# 06-BatteryManagement.net
KiCad netlist of a schematic drawn in Altium Designer
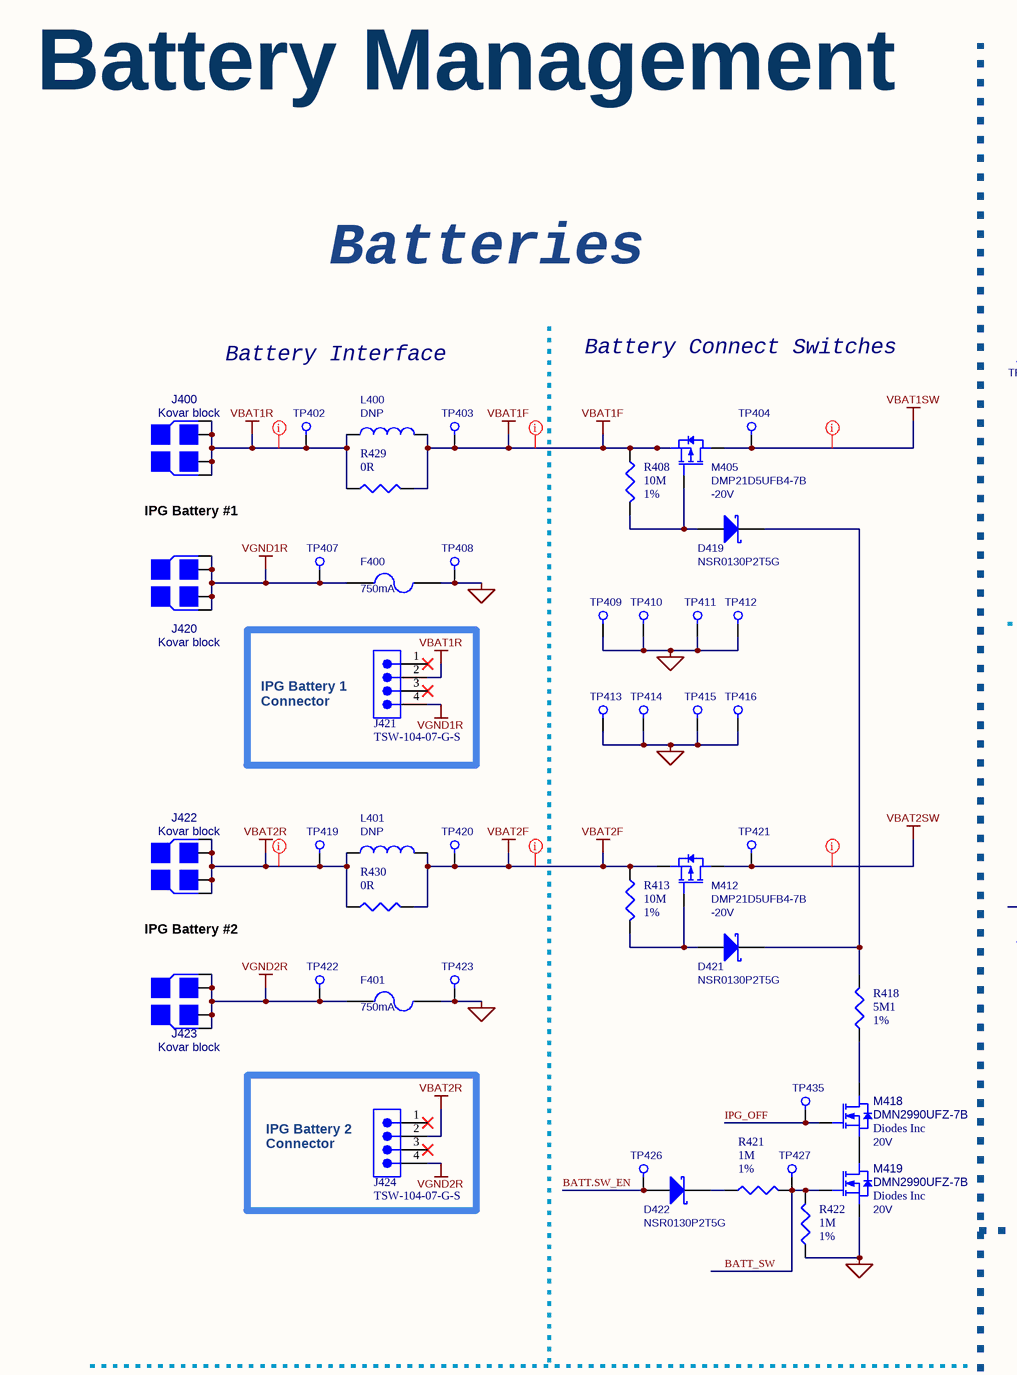
[diagram p0: 06-BatteryManagement.SchDoc, left]
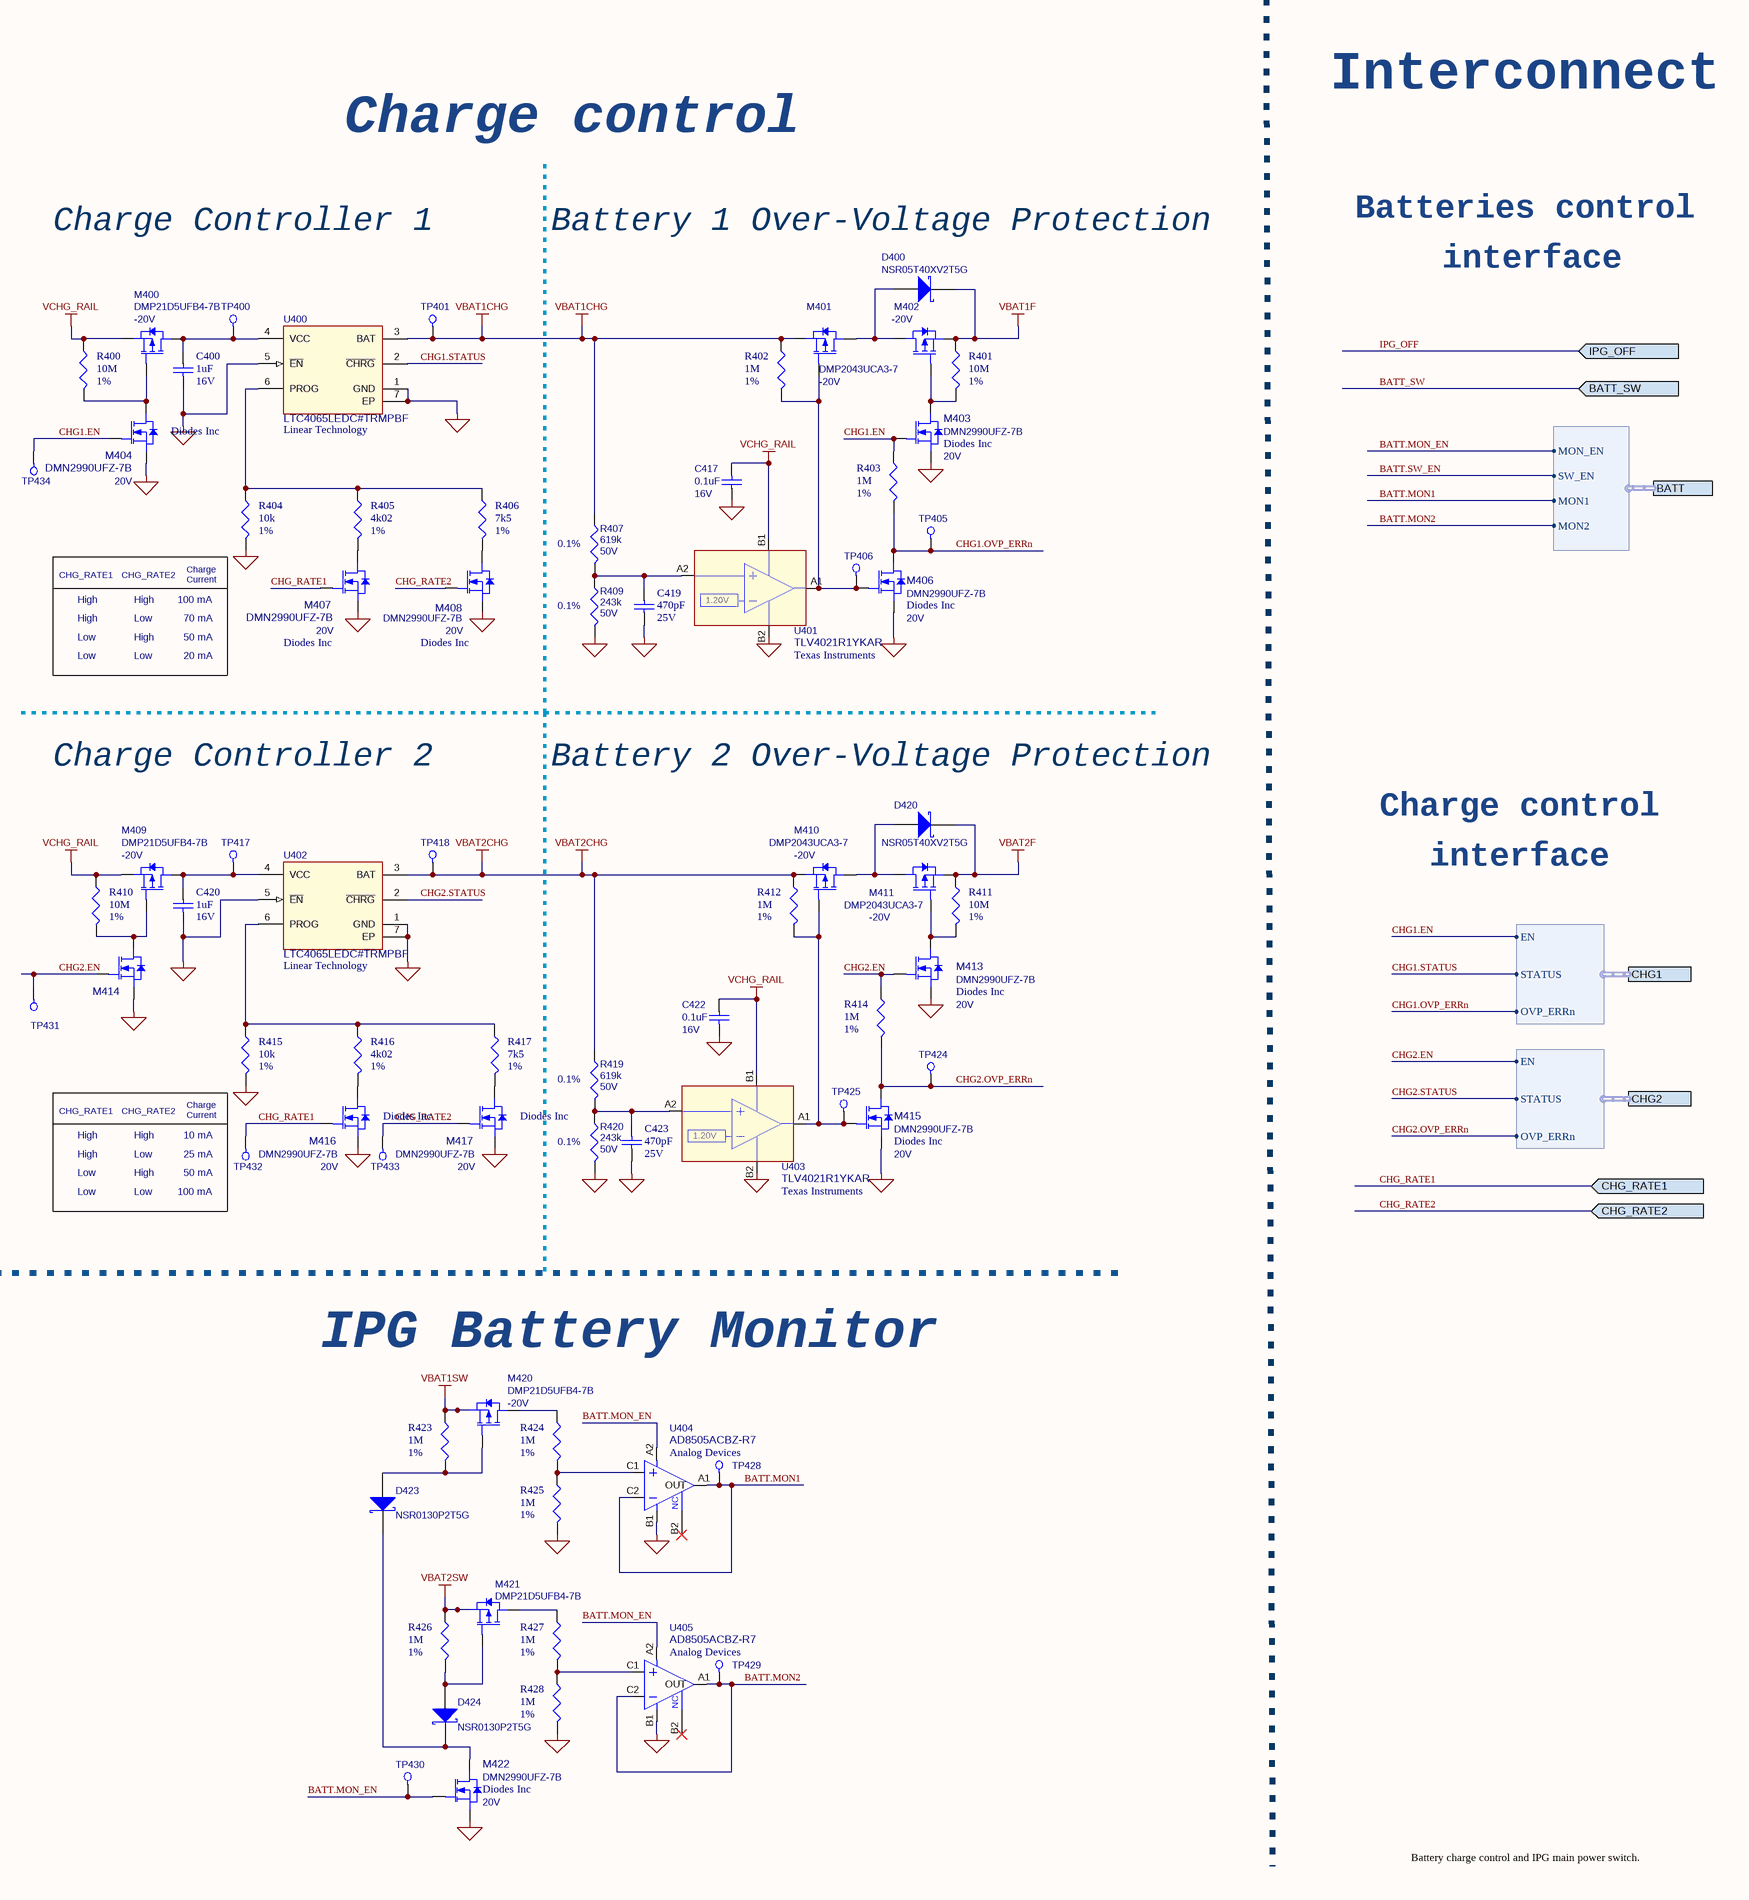
[diagram p1: 06-BatteryManagement.SchDoc, right]

(export (version "E")
  (design (tool "Eeschema 10.0.6"))
  (components
    (comp (ref "C400")
      (value "1uF")
      (footprint "C0201_C")
      (fields
        (field (name "MANUFACTURER") "Murata")
        (field (name "MANUFACTURER PART NUMBER") "GRM033R61C105ME15D")
        (field (name "RATED DC VOLTAGE (URDC)") "16V")
      )
      (libsource (lib "MP-LIBRARY") (part "GRM033R61C105ME15D"))
    )
    (comp (ref "C417")
      (value "0.1uF")
      (footprint "CAP0402_REDUCED")
      (description "Capacitor, 0.1uF, X7R, 16V, 10%, 0402, Implant-grade")
      (fields
        (field (name "MANUFACTURER") "Murata")
        (field (name "RATING") "16V")
        (field (name "MANUFACTURER PART NUMBER") "GCM155R71C104KA55")
      )
      (libsource (lib "MP-LIBRARY") (part "GCM155R71C104KA55"))
    )
    (comp (ref "C419")
      (value "470pF")
      (footprint "C0201_C")
      (fields
        (field (name "MANUFACTURER") "Murata")
        (field (name "MANUFACTURER PART NUMBER") "GCM033R71E471KA03D")
        (field (name "RATED DC VOLTAGE (URDC)") "25V")
      )
      (libsource (lib "MP-LIBRARY") (part "GCM033R71E471KA03D"))
    )
    (comp (ref "C420")
      (value "1uF")
      (footprint "C0201_C")
      (fields
        (field (name "MANUFACTURER") "Murata")
        (field (name "MANUFACTURER PART NUMBER") "GRM033R61C105ME15D")
        (field (name "RATED DC VOLTAGE (URDC)") "16V")
      )
      (libsource (lib "MP-LIBRARY") (part "GRM033R61C105ME15D"))
    )
    (comp (ref "C422")
      (value "0.1uF")
      (footprint "CAP0402_REDUCED")
      (description "Capacitor, 0.1uF, X7R, 16V, 10%, 0402, Implant-grade")
      (fields
        (field (name "MANUFACTURER") "Murata")
        (field (name "RATING") "16V")
        (field (name "MANUFACTURER PART NUMBER") "GCM155R71C104KA55")
      )
      (libsource (lib "MP-LIBRARY") (part "GCM155R71C104KA55"))
    )
    (comp (ref "C423")
      (value "470pF")
      (footprint "C0201_C")
      (fields
        (field (name "MANUFACTURER") "Murata")
        (field (name "MANUFACTURER PART NUMBER") "GCM033R71E471KA03D")
        (field (name "RATED DC VOLTAGE (URDC)") "25V")
      )
      (libsource (lib "MP-LIBRARY") (part "GCM033R71E471KA03D"))
    )
    (comp (ref "D400")
      (value "NSR05T40XV2T5G")
      (footprint "STM_SOD-523_R")
      (description "Schottky, 40V, 500mA, 530mV, SOD-523")
      (fields (field (name "MANUFACTURER") "ON Semiconductor"))
      (libsource (lib "MP-LIBRARY") (part "NSR05T40XV2T5G"))
    )
    (comp (ref "D419")
      (value "NSR0130P2T5G")
      (footprint "ONSC_SOD-923_CASE514AB")
      (description "Schottky, 30V, 100mA, 385mV, 200mW, SOD-923")
      (fields (field (name "MANUFACTURER") "ON Semiconductor"))
      (libsource (lib "MP-LIBRARY") (part "NSR0130P2T5G"))
    )
    (comp (ref "D420")
      (value "NSR05T40XV2T5G")
      (footprint "STM_SOD-523_R")
      (description "Schottky, 40V, 500mA, 530mV, SOD-523")
      (fields (field (name "MANUFACTURER") "ON Semiconductor"))
      (libsource (lib "MP-LIBRARY") (part "NSR05T40XV2T5G"))
    )
    (comp (ref "D421")
      (value "NSR0130P2T5G")
      (footprint "ONSC_SOD-923_CASE514AB")
      (description "Schottky, 30V, 100mA, 385mV, 200mW, SOD-923")
      (fields (field (name "MANUFACTURER") "ON Semiconductor"))
      (libsource (lib "MP-LIBRARY") (part "NSR0130P2T5G"))
    )
    (comp (ref "D422")
      (value "NSR0130P2T5G")
      (footprint "ONSC_SOD-923_CASE514AB")
      (description "Schottky, 30V, 100mA, 385mV, 200mW, SOD-923")
      (fields (field (name "MANUFACTURER") "ON Semiconductor"))
      (libsource (lib "MP-LIBRARY") (part "NSR0130P2T5G"))
    )
    (comp (ref "D423")
      (value "NSR0130P2T5G")
      (footprint "ONSC_SOD-923_CASE514AB")
      (description "Schottky, 30V, 100mA, 385mV, 200mW, SOD-923")
      (fields (field (name "MANUFACTURER") "ON Semiconductor"))
      (libsource (lib "MP-LIBRARY") (part "NSR0130P2T5G"))
    )
    (comp (ref "D424")
      (value "NSR0130P2T5G")
      (footprint "ONSC_SOD-923_CASE514AB")
      (description "Schottky, 30V, 100mA, 385mV, 200mW, SOD-923")
      (fields (field (name "MANUFACTURER") "ON Semiconductor"))
      (libsource (lib "MP-LIBRARY") (part "NSR0130P2T5G"))
    )
    (comp (ref "F400")
      (value "750mA")
      (footprint "LITTELFUSE_440series_1206_REDUCED")
      (description "Fuse, 750mA, 63V, 1206")
      (fields
        (field (name "MANUFACTURER") "Littelfuse")
        (field (name "MANUFACTURER PART NUMBER") "0440.750WR")
      )
      (libsource (lib "MP-LIBRARY") (part "0440.750WR"))
    )
    (comp (ref "F401")
      (value "750mA")
      (footprint "LITTELFUSE_440series_1206_REDUCED")
      (description "Fuse, 750mA, 63V, 1206")
      (fields
        (field (name "MANUFACTURER") "Littelfuse")
        (field (name "MANUFACTURER PART NUMBER") "0440.750WR")
      )
      (libsource (lib "MP-LIBRARY") (part "0440.750WR"))
    )
    (comp (ref "J400")
      (value "Kovar block")
      (footprint "KOVAR_BLOCK_PAD_1.53MM")
      (description "Kovar block, TBD")
      (fields (field (name "MANUFACTURER") "TBD") (field (name "Comment") "Kovar Block"))
      (libsource (lib "MP-LIBRARY") (part "Kovar Block"))
    )
    (comp (ref "J420")
      (value "Kovar block")
      (footprint "KOVAR_BLOCK_PAD_1.53MM")
      (description "Kovar block, TBD")
      (fields (field (name "MANUFACTURER") "TBD") (field (name "Comment") "Kovar Block"))
      (libsource (lib "MP-LIBRARY") (part "Kovar Block"))
    )
    (comp (ref "J421")
      (value "TSW-104-07-G-S")
      (footprint "SMTC-TSW-104-07-X-S")
      (fields (field (name "MANUFACTURER") "Samtec") (field (name "PARTNUMBER") "TSW-106-07-G-S"))
      (libsource (lib "MP-LIBRARY") (part "TSW-104-07-G-S"))
    )
    (comp (ref "J422")
      (value "Kovar block")
      (footprint "KOVAR_BLOCK_PAD_1.53MM")
      (description "Kovar block, TBD")
      (fields (field (name "MANUFACTURER") "TBD") (field (name "Comment") "Kovar Block"))
      (libsource (lib "MP-LIBRARY") (part "Kovar Block"))
    )
    (comp (ref "J423")
      (value "Kovar block")
      (footprint "KOVAR_BLOCK_PAD_1.53MM")
      (description "Kovar block, TBD")
      (fields (field (name "MANUFACTURER") "TBD") (field (name "Comment") "Kovar Block"))
      (libsource (lib "MP-LIBRARY") (part "Kovar Block"))
    )
    (comp (ref "J424")
      (value "TSW-104-07-G-S")
      (footprint "SMTC-TSW-104-07-X-S")
      (fields (field (name "MANUFACTURER") "Samtec") (field (name "PARTNUMBER") "TSW-106-07-G-S"))
      (libsource (lib "MP-LIBRARY") (part "TSW-104-07-G-S"))
    )
    (comp (ref "L400")
      (value "DNP")
      (footprint "L0402_C")
      (description "DNP: Inductor, DNP, 0402")
      (libsource (lib "MP-LIBRARY") (part "IND_DNP_0402"))
    )
    (comp (ref "L401")
      (value "DNP")
      (footprint "L0402_C")
      (description "DNP: Inductor, DNP, 0402")
      (libsource (lib "MP-LIBRARY") (part "IND_DNP_0402"))
    )
    (comp (ref "M400")
      (value "DMP21D5UFB4-7B")
      (footprint "DIODESINC_X2-DFN1006-3_REDUCED")
      (description "MOSFET, P-chan, -20V, -400mA, X2-DFN1006-3")
      (fields (field (name "MANUFACTURER") "Diodes Inc") (field (name "RATING") "-20V"))
      (libsource (lib "MP-LIBRARY") (part "DMP21D5UFB4-7B"))
    )
    (comp (ref "M401")
      (value "DMP2043UCA3-7")
      (footprint "DIODESINC_X2-DSN1010-3_CUSTOMPIN")
      (description "MOSFET, P-chan, -20V, -3.4A, DFN1010-3")
      (fields (field (name "MANUFACTURER") "Diodes Inc") (field (name "RATING") "-20V"))
      (libsource (lib "MP-LIBRARY") (part "DMP2043UCA3-7"))
    )
    (comp (ref "M402")
      (value "DMP2043UCA3-7")
      (footprint "DIODESINC_X2-DSN1010-3_CUSTOMPIN")
      (description "MOSFET, P-chan, -20V, -3.4A, DFN1010-3")
      (fields (field (name "MANUFACTURER") "Diodes Inc") (field (name "RATING") "-20V"))
      (libsource (lib "MP-LIBRARY") (part "DMP2043UCA3-7"))
    )
    (comp (ref "M403")
      (value "DMN2990UFZ-7B")
      (footprint "DIODESINC_X2-DFN0606-3")
      (description "MOSFET, N-Chan, 20V, 170mA, DFN0606")
      (fields (field (name "MANUFACTURER") "Diodes Inc") (field (name "RATING") "20V"))
      (libsource (lib "MP-LIBRARY") (part "DMN2990UFZ-7B"))
    )
    (comp (ref "M404")
      (value "DMN2990UFZ-7B")
      (footprint "DIODESINC_X2-DFN0606-3")
      (description "MOSFET, N-Chan, 20V, 170mA, DFN0606")
      (fields (field (name "RATING") "20V") (field (name "MANUFACTURER") "Diodes Inc"))
      (libsource (lib "MP-LIBRARY") (part "DMN2990UFZ-7B"))
    )
    (comp (ref "M405")
      (value "DMP21D5UFB4-7B")
      (footprint "DIODESINC_X2-DFN1006-3_REDUCED")
      (description "MOSFET, P-chan, -20V, -400mA, X2-DFN1006-3")
      (fields (field (name "MANUFACTURER") "Diodes Inc") (field (name "RATING") "-20V"))
      (libsource (lib "MP-LIBRARY") (part "DMP21D5UFB4-7B"))
    )
    (comp (ref "M406")
      (value "DMN2990UFZ-7B")
      (footprint "DIODESINC_X2-DFN0606-3")
      (description "MOSFET, N-Chan, 20V, 170mA, DFN0606")
      (fields (field (name "MANUFACTURER") "Diodes Inc") (field (name "RATING") "20V"))
      (libsource (lib "MP-LIBRARY") (part "DMN2990UFZ-7B"))
    )
    (comp (ref "M407")
      (value "DMN2990UFZ-7B")
      (footprint "DIODESINC_X2-DFN0606-3")
      (description "MOSFET, N-Chan, 20V, 170mA, DFN0606")
      (fields (field (name "RATING") "20V") (field (name "MANUFACTURER") "Diodes Inc"))
      (libsource (lib "MP-LIBRARY") (part "DMN2990UFZ-7B"))
    )
    (comp (ref "M408")
      (value "DMN2990UFZ-7B")
      (footprint "DIODESINC_X2-DFN0606-3")
      (description "MOSFET, N-Chan, 20V, 170mA, DFN0606")
      (fields (field (name "RATING") "20V") (field (name "MANUFACTURER") "Diodes Inc"))
      (libsource (lib "MP-LIBRARY") (part "DMN2990UFZ-7B"))
    )
    (comp (ref "M409")
      (value "DMP21D5UFB4-7B")
      (footprint "DIODESINC_X2-DFN1006-3_REDUCED")
      (description "MOSFET, P-chan, -20V, -400mA, X2-DFN1006-3")
      (fields (field (name "MANUFACTURER") "Diodes Inc") (field (name "RATING") "-20V"))
      (libsource (lib "MP-LIBRARY") (part "DMP21D5UFB4-7B"))
    )
    (comp (ref "M410")
      (value "DMP2043UCA3-7")
      (footprint "DIODESINC_X2-DSN1010-3_CUSTOMPIN")
      (description "MOSFET, P-chan, -20V, -3.4A, DFN1010-3")
      (fields (field (name "MANUFACTURER") "Diodes Inc") (field (name "RATING") "-20V"))
      (libsource (lib "MP-LIBRARY") (part "DMP2043UCA3-7"))
    )
    (comp (ref "M411")
      (value "DMP2043UCA3-7")
      (footprint "DIODESINC_X2-DSN1010-3_CUSTOMPIN")
      (description "MOSFET, P-chan, -20V, -3.4A, DFN1010-3")
      (fields (field (name "MANUFACTURER") "Diodes Inc") (field (name "RATING") "-20V"))
      (libsource (lib "MP-LIBRARY") (part "DMP2043UCA3-7"))
    )
    (comp (ref "M412")
      (value "DMP21D5UFB4-7B")
      (footprint "DIODESINC_X2-DFN1006-3_REDUCED")
      (description "MOSFET, P-chan, -20V, -400mA, X2-DFN1006-3")
      (fields (field (name "MANUFACTURER") "Diodes Inc") (field (name "RATING") "-20V"))
      (libsource (lib "MP-LIBRARY") (part "DMP21D5UFB4-7B"))
    )
    (comp (ref "M413")
      (value "DMN2990UFZ-7B")
      (footprint "DIODESINC_X2-DFN0606-3")
      (description "MOSFET, N-Chan, 20V, 170mA, DFN0606")
      (fields (field (name "MANUFACTURER") "Diodes Inc") (field (name "RATING") "20V"))
      (libsource (lib "MP-LIBRARY") (part "DMN2990UFZ-7B"))
    )
    (comp (ref "M414")
      (value "DMN2990UFZ-7B")
      (footprint "DIODESINC_X2-DFN0606-3")
      (description "MOSFET, N-Chan, 20V, 170mA, DFN0606")
      (fields (field (name "MANUFACTURER") "Diodes Inc"))
      (libsource (lib "MP-LIBRARY") (part "DMN2990UFZ-7B"))
    )
    (comp (ref "M415")
      (value "DMN2990UFZ-7B")
      (footprint "DIODESINC_X2-DFN0606-3")
      (description "MOSFET, N-Chan, 20V, 170mA, DFN0606")
      (fields (field (name "MANUFACTURER") "Diodes Inc") (field (name "RATING") "20V"))
      (libsource (lib "MP-LIBRARY") (part "DMN2990UFZ-7B"))
    )
    (comp (ref "M416")
      (value "DMN2990UFZ-7B")
      (footprint "DIODESINC_X2-DFN0606-3")
      (description "MOSFET, N-Chan, 20V, 170mA, DFN0606")
      (fields (field (name "RATING") "20V") (field (name "MANUFACTURER") "Diodes Inc"))
      (libsource (lib "MP-LIBRARY") (part "DMN2990UFZ-7B"))
    )
    (comp (ref "M417")
      (value "DMN2990UFZ-7B")
      (footprint "DIODESINC_X2-DFN0606-3")
      (description "MOSFET, N-Chan, 20V, 170mA, DFN0606")
      (fields (field (name "RATING") "20V") (field (name "MANUFACTURER") "Diodes Inc"))
      (libsource (lib "MP-LIBRARY") (part "DMN2990UFZ-7B"))
    )
    (comp (ref "M418")
      (value "DMN2990UFZ-7B")
      (footprint "DIODESINC_X2-DFN0606-3")
      (description "MOSFET, N-Chan, 20V, 170mA, DFN0606")
      (fields (field (name "MANUFACTURER") "Diodes Inc") (field (name "RATING") "20V"))
      (libsource (lib "MP-LIBRARY") (part "DMN2990UFZ-7B"))
    )
    (comp (ref "M419")
      (value "DMN2990UFZ-7B")
      (footprint "DIODESINC_X2-DFN0606-3")
      (description "MOSFET, N-Chan, 20V, 170mA, DFN0606")
      (fields (field (name "MANUFACTURER") "Diodes Inc") (field (name "RATING") "20V"))
      (libsource (lib "MP-LIBRARY") (part "DMN2990UFZ-7B"))
    )
    (comp (ref "M420")
      (value "DMP21D5UFB4-7B")
      (footprint "DIODESINC_X2-DFN1006-3_REDUCED")
      (description "MOSFET, P-chan, -20V, -400mA, X2-DFN1006-3")
      (fields (field (name "MANUFACTURER") "Diodes Inc") (field (name "RATING") "-20V"))
      (libsource (lib "MP-LIBRARY") (part "DMP21D5UFB4-7B"))
    )
    (comp (ref "M421")
      (value "DMP21D5UFB4-7B")
      (footprint "DIODESINC_X2-DFN1006-3_REDUCED")
      (description "MOSFET, P-chan, -20V, -400mA, X2-DFN1006-3")
      (fields (field (name "MANUFACTURER") "Diodes Inc"))
      (libsource (lib "MP-LIBRARY") (part "DMP21D5UFB4-7B"))
    )
    (comp (ref "M422")
      (value "DMN2990UFZ-7B")
      (footprint "DIODESINC_X2-DFN0606-3")
      (description "MOSFET, N-Chan, 20V, 170mA, DFN0606")
      (fields (field (name "MANUFACTURER") "Diodes Inc") (field (name "RATING") "20V"))
      (libsource (lib "MP-LIBRARY") (part "DMN2990UFZ-7B"))
    )
    (comp (ref "R400")
      (value "10M")
      (footprint "R0201_C")
      (fields
        (field (name "MANUFACTURER") "Vishay Draloric")
        (field (name "MANUFACTURER PART NUMBER") "CRCW020110M0FNED")
        (field (name "TOLERANCE") "1%")
        (field (name "POWER") "50mW")
      )
      (libsource (lib "MP-LIBRARY") (part "CRCW020110M0FNED"))
    )
    (comp (ref "R401")
      (value "10M")
      (footprint "R0201_C")
      (fields
        (field (name "MANUFACTURER") "Vishay Draloric")
        (field (name "MANUFACTURER PART NUMBER") "CRCW020110M0FNED")
        (field (name "TOLERANCE") "1%")
        (field (name "POWER") "50mW")
      )
      (libsource (lib "MP-LIBRARY") (part "CRCW020110M0FNED"))
    )
    (comp (ref "R402")
      (value "1M")
      (footprint "R0201_C")
      (fields
        (field (name "MANUFACTURER") "Vishay")
        (field (name "MANUFACTURER PART NUMBER") "CRCW02011M00FNED")
        (field (name "TOLERANCE") "1%")
        (field (name "POWER") "50mW")
      )
      (libsource (lib "MP-LIBRARY") (part "CRCW02011M00FNED"))
    )
    (comp (ref "R403")
      (value "1M")
      (footprint "R0201_C")
      (fields
        (field (name "MANUFACTURER") "Vishay")
        (field (name "MANUFACTURER PART NUMBER") "CRCW02011M00FNED")
        (field (name "TOLERANCE") "1%")
        (field (name "POWER") "50mW")
      )
      (libsource (lib "MP-LIBRARY") (part "CRCW02011M00FNED"))
    )
    (comp (ref "R404")
      (value "10k")
      (footprint "R0201_C")
      (fields
        (field (name "MANUFACTURER") "Vishay")
        (field (name "MANUFACTURER PART NUMBER") "CRCW020110K0FNED")
        (field (name "TOLERANCE") "1%")
        (field (name "POWER") "50mW")
      )
      (libsource (lib "MP-LIBRARY") (part "CRCW020110K0FNED"))
    )
    (comp (ref "R405")
      (value "4k02")
      (footprint "R0201_C")
      (fields
        (field (name "MANUFACTURER") "Vishay")
        (field (name "MANUFACTURER PART NUMBER") "CRCW02014K02FNED")
        (field (name "TOLERANCE") "1%")
        (field (name "POWER") "50mW")
      )
      (libsource (lib "MP-LIBRARY") (part "CRCW02014K02FNED"))
    )
    (comp (ref "R406")
      (value "7k5")
      (footprint "R0201_C")
      (fields
        (field (name "MANUFACTURER") "Vishay")
        (field (name "MANUFACTURER PART NUMBER") "CRCW02017K50FNED")
        (field (name "TOLERANCE") "1%")
        (field (name "POWER") "50mW")
      )
      (libsource (lib "MP-LIBRARY") (part "CRCW02017K50FNED"))
    )
    (comp (ref "R407")
      (value "619k")
      (footprint "RES0402_REDUCED")
      (description "Resistor, 619k, 0.1%, 0402")
      (fields
        (field (name "MANUFACTURER") "Vishay")
        (field (name "RATING") "50V")
        (field (name "PRECISION") "0.1%")
        (field (name "MANUFACTURER PART NUMBER") "MCS0402MD6193BE000")
      )
      (libsource (lib "MP-LIBRARY") (part "MCS0402MD6193BE000"))
    )
    (comp (ref "R408")
      (value "10M")
      (footprint "R0201_C")
      (fields
        (field (name "MANUFACTURER") "Vishay Draloric")
        (field (name "MANUFACTURER PART NUMBER") "CRCW020110M0FNED")
        (field (name "TOLERANCE") "1%")
        (field (name "POWER") "50mW")
      )
      (libsource (lib "MP-LIBRARY") (part "CRCW020110M0FNED"))
    )
    (comp (ref "R409")
      (value "243k")
      (footprint "RES0402_REDUCED")
      (description "Resistor, 243k, 0.1%, 0402")
      (fields
        (field (name "MANUFACTURER") "TE Connectivity")
        (field (name "RATING") "50V")
        (field (name "PRECISION") "0.1%")
        (field (name "MANUFACTURER PART NUMBER") "RP73PF1E243KBTDF")
      )
      (libsource (lib "MP-LIBRARY") (part "RP73PF1E243KBTD"))
    )
    (comp (ref "R410")
      (value "10M")
      (footprint "R0201_C")
      (fields
        (field (name "MANUFACTURER") "Vishay Draloric")
        (field (name "MANUFACTURER PART NUMBER") "CRCW020110M0FNED")
        (field (name "TOLERANCE") "1%")
        (field (name "POWER") "50mW")
      )
      (libsource (lib "MP-LIBRARY") (part "CRCW020110M0FNED"))
    )
    (comp (ref "R411")
      (value "10M")
      (footprint "R0201_C")
      (fields
        (field (name "MANUFACTURER") "Vishay Draloric")
        (field (name "MANUFACTURER PART NUMBER") "CRCW020110M0FNED")
        (field (name "TOLERANCE") "1%")
        (field (name "POWER") "50mW")
      )
      (libsource (lib "MP-LIBRARY") (part "CRCW020110M0FNED"))
    )
    (comp (ref "R412")
      (value "1M")
      (footprint "R0201_C")
      (fields
        (field (name "MANUFACTURER") "Vishay")
        (field (name "MANUFACTURER PART NUMBER") "CRCW02011M00FNED")
        (field (name "TOLERANCE") "1%")
        (field (name "POWER") "50mW")
      )
      (libsource (lib "MP-LIBRARY") (part "CRCW02011M00FNED"))
    )
    (comp (ref "R413")
      (value "10M")
      (footprint "R0201_C")
      (fields
        (field (name "MANUFACTURER") "Vishay Draloric")
        (field (name "MANUFACTURER PART NUMBER") "CRCW020110M0FNED")
        (field (name "TOLERANCE") "1%")
        (field (name "POWER") "50mW")
      )
      (libsource (lib "MP-LIBRARY") (part "CRCW020110M0FNED"))
    )
    (comp (ref "R414")
      (value "1M")
      (footprint "R0201_C")
      (fields
        (field (name "MANUFACTURER") "Vishay")
        (field (name "MANUFACTURER PART NUMBER") "CRCW02011M00FNED")
        (field (name "TOLERANCE") "1%")
        (field (name "POWER") "50mW")
      )
      (libsource (lib "MP-LIBRARY") (part "CRCW02011M00FNED"))
    )
    (comp (ref "R415")
      (value "10k")
      (footprint "R0201_C")
      (fields
        (field (name "MANUFACTURER") "Vishay")
        (field (name "MANUFACTURER PART NUMBER") "CRCW020110K0FNED")
        (field (name "TOLERANCE") "1%")
        (field (name "POWER") "50mW")
      )
      (libsource (lib "MP-LIBRARY") (part "CRCW020110K0FNED"))
    )
    (comp (ref "R416")
      (value "4k02")
      (footprint "R0201_C")
      (fields
        (field (name "MANUFACTURER") "Vishay")
        (field (name "MANUFACTURER PART NUMBER") "CRCW02014K02FNED")
        (field (name "TOLERANCE") "1%")
        (field (name "POWER") "50mW")
      )
      (libsource (lib "MP-LIBRARY") (part "CRCW02014K02FNED"))
    )
    (comp (ref "R417")
      (value "7k5")
      (footprint "R0201_C")
      (fields
        (field (name "MANUFACTURER") "Vishay")
        (field (name "MANUFACTURER PART NUMBER") "CRCW02017K50FNED")
        (field (name "TOLERANCE") "1%")
        (field (name "POWER") "50mW")
      )
      (libsource (lib "MP-LIBRARY") (part "CRCW02017K50FNED"))
    )
    (comp (ref "R418")
      (value "5M1")
      (footprint "R0201_C")
      (fields
        (field (name "MANUFACTURER") "Vishay Draloric")
        (field (name "MANUFACTURER PART NUMBER") "CRCW02015M10FNED")
        (field (name "TOLERANCE") "1%")
        (field (name "POWER") "50mW")
      )
      (libsource (lib "MP-LIBRARY") (part "CRCW02015M10FNED"))
    )
    (comp (ref "R419")
      (value "619k")
      (footprint "RES0402_REDUCED")
      (description "Resistor, 619k, 0.1%, 0402")
      (fields
        (field (name "MANUFACTURER") "Vishay")
        (field (name "RATING") "50V")
        (field (name "PRECISION") "0.1%")
        (field (name "MANUFACTURER PART NUMBER") "MCS0402MD6193BE000")
      )
      (libsource (lib "MP-LIBRARY") (part "MCS0402MD6193BE000"))
    )
    (comp (ref "R420")
      (value "243k")
      (footprint "RES0402_REDUCED")
      (description "Resistor, 243k, 0.1%, 0402")
      (fields
        (field (name "MANUFACTURER") "TE Connectivity")
        (field (name "RATING") "50V")
        (field (name "PRECISION") "0.1%")
        (field (name "MANUFACTURER PART NUMBER") "RP73PF1E243KBTDF")
      )
      (libsource (lib "MP-LIBRARY") (part "RP73PF1E243KBTD"))
    )
    (comp (ref "R421")
      (value "1M")
      (footprint "R0201_C")
      (fields
        (field (name "MANUFACTURER") "Vishay")
        (field (name "MANUFACTURER PART NUMBER") "CRCW02011M00FNED")
        (field (name "TOLERANCE") "1%")
        (field (name "POWER") "50mW")
      )
      (libsource (lib "MP-LIBRARY") (part "CRCW02011M00FNED"))
    )
    (comp (ref "R422")
      (value "1M")
      (footprint "R0201_C")
      (fields
        (field (name "MANUFACTURER") "Vishay")
        (field (name "MANUFACTURER PART NUMBER") "CRCW02011M00FNED")
        (field (name "TOLERANCE") "1%")
        (field (name "POWER") "50mW")
      )
      (libsource (lib "MP-LIBRARY") (part "CRCW02011M00FNED"))
    )
    (comp (ref "R423")
      (value "1M")
      (footprint "R0201_C")
      (fields
        (field (name "MANUFACTURER") "Vishay")
        (field (name "MANUFACTURER PART NUMBER") "CRCW02011M00FNED")
        (field (name "TOLERANCE") "1%")
        (field (name "POWER") "50mW")
      )
      (libsource (lib "MP-LIBRARY") (part "CRCW02011M00FNED"))
    )
    (comp (ref "R424")
      (value "1M")
      (footprint "R0201_C")
      (fields
        (field (name "MANUFACTURER") "Vishay")
        (field (name "MANUFACTURER PART NUMBER") "CRCW02011M00FNED")
        (field (name "TOLERANCE") "1%")
        (field (name "POWER") "50mW")
      )
      (libsource (lib "MP-LIBRARY") (part "CRCW02011M00FNED"))
    )
    (comp (ref "R425")
      (value "1M")
      (footprint "R0201_C")
      (fields
        (field (name "MANUFACTURER") "Vishay")
        (field (name "MANUFACTURER PART NUMBER") "CRCW02011M00FNED")
        (field (name "TOLERANCE") "1%")
        (field (name "POWER") "50mW")
      )
      (libsource (lib "MP-LIBRARY") (part "CRCW02011M00FNED"))
    )
    (comp (ref "R426")
      (value "1M")
      (footprint "R0201_C")
      (fields
        (field (name "MANUFACTURER") "Vishay")
        (field (name "MANUFACTURER PART NUMBER") "CRCW02011M00FNED")
        (field (name "TOLERANCE") "1%")
        (field (name "POWER") "50mW")
      )
      (libsource (lib "MP-LIBRARY") (part "CRCW02011M00FNED"))
    )
    (comp (ref "R427")
      (value "1M")
      (footprint "R0201_C")
      (fields
        (field (name "MANUFACTURER") "Vishay")
        (field (name "MANUFACTURER PART NUMBER") "CRCW02011M00FNED")
        (field (name "TOLERANCE") "1%")
        (field (name "POWER") "50mW")
      )
      (libsource (lib "MP-LIBRARY") (part "CRCW02011M00FNED"))
    )
    (comp (ref "R428")
      (value "1M")
      (footprint "R0201_C")
      (fields
        (field (name "MANUFACTURER") "Vishay")
        (field (name "MANUFACTURER PART NUMBER") "CRCW02011M00FNED")
        (field (name "TOLERANCE") "1%")
        (field (name "POWER") "50mW")
      )
      (libsource (lib "MP-LIBRARY") (part "CRCW02011M00FNED"))
    )
    (comp (ref "R429")
      (value "0R")
      (footprint "R0201_C")
      (description "Fixed Resistor, Metal Glaze/thick Film, 0.05W, 0ohm, Surface Mount, 0201")
      (fields
        (field (name "MANUFACTURER") "Vishay")
        (field (name "MANUFACTURER PART NUMBER") "CRCW02010000Z0ED")
      )
      (libsource (lib "MP-LIBRARY") (part "CRCW02010000Z0ED"))
    )
    (comp (ref "R430")
      (value "0R")
      (footprint "R0201_C")
      (description "Fixed Resistor, Metal Glaze/thick Film, 0.05W, 0ohm, Surface Mount, 0201")
      (fields
        (field (name "MANUFACTURER") "Vishay")
        (field (name "MANUFACTURER PART NUMBER") "CRCW02010000Z0ED")
      )
      (libsource (lib "MP-LIBRARY") (part "CRCW02010000Z0ED"))
    )
    (comp (ref "TP400")
      (value "Test Point")
      (footprint "testpad_0.9mm")
      (description "Test pad, 0.90mm circular pad")
      (libsource (lib "MP-LIBRARY") (part "Test Point"))
    )
    (comp (ref "TP401")
      (value "Test Point")
      (footprint "testpad_0.9mm")
      (description "Test pad, 0.90mm circular pad")
      (libsource (lib "MP-LIBRARY") (part "Test Point"))
    )
    (comp (ref "TP402")
      (value "Test Point")
      (footprint "testpad_0.9mm")
      (description "Test pad, 0.90mm circular pad")
      (libsource (lib "MP-LIBRARY") (part "Test Point"))
    )
    (comp (ref "TP403")
      (value "Test Point")
      (footprint "testpad_0.9mm")
      (description "Test pad, 0.90mm circular pad")
      (libsource (lib "MP-LIBRARY") (part "Test Point"))
    )
    (comp (ref "TP404")
      (value "Test Point")
      (footprint "testpad_0.9mm")
      (description "Test pad, 0.90mm circular pad")
      (libsource (lib "MP-LIBRARY") (part "Test Point"))
    )
    (comp (ref "TP405")
      (value "Test Point")
      (footprint "testpad_0.9mm")
      (description "Test pad, 0.90mm circular pad")
      (libsource (lib "MP-LIBRARY") (part "Test Point"))
    )
    (comp (ref "TP406")
      (value "Test Point")
      (footprint "testpad_0.9mm")
      (description "Test pad, 0.90mm circular pad")
      (libsource (lib "MP-LIBRARY") (part "Test Point"))
    )
    (comp (ref "TP407")
      (value "Test Point")
      (footprint "testpad_0.9mm")
      (description "Test pad, 0.90mm circular pad")
      (libsource (lib "MP-LIBRARY") (part "Test Point"))
    )
    (comp (ref "TP408")
      (value "Test Point")
      (footprint "testpad_0.9mm")
      (description "Test pad, 0.90mm circular pad")
      (libsource (lib "MP-LIBRARY") (part "Test Point"))
    )
    (comp (ref "TP409")
      (value "Test Point")
      (footprint "testpad_0.9mm")
      (description "Test pad, 0.90mm circular pad")
      (libsource (lib "MP-LIBRARY") (part "Test Point"))
    )
    (comp (ref "TP410")
      (value "Test Point")
      (footprint "testpad_0.9mm")
      (description "Test pad, 0.90mm circular pad")
      (libsource (lib "MP-LIBRARY") (part "Test Point"))
    )
    (comp (ref "TP411")
      (value "Test Point")
      (footprint "testpad_0.9mm")
      (description "Test pad, 0.90mm circular pad")
      (libsource (lib "MP-LIBRARY") (part "Test Point"))
    )
    (comp (ref "TP412")
      (value "Test Point")
      (footprint "testpad_0.9mm")
      (description "Test pad, 0.90mm circular pad")
      (libsource (lib "MP-LIBRARY") (part "Test Point"))
    )
    (comp (ref "TP413")
      (value "Test Point")
      (footprint "testpad_0.9mm")
      (description "Test pad, 0.90mm circular pad")
      (libsource (lib "MP-LIBRARY") (part "Test Point"))
    )
    (comp (ref "TP414")
      (value "Test Point")
      (footprint "testpad_0.9mm")
      (description "Test pad, 0.90mm circular pad")
      (libsource (lib "MP-LIBRARY") (part "Test Point"))
    )
    (comp (ref "TP415")
      (value "Test Point")
      (footprint "testpad_0.9mm")
      (description "Test pad, 0.90mm circular pad")
      (libsource (lib "MP-LIBRARY") (part "Test Point"))
    )
    (comp (ref "TP416")
      (value "Test Point")
      (footprint "testpad_0.9mm")
      (description "Test pad, 0.90mm circular pad")
      (libsource (lib "MP-LIBRARY") (part "Test Point"))
    )
    (comp (ref "TP417")
      (value "Test Point")
      (footprint "testpad_0.9mm")
      (description "Test pad, 0.90mm circular pad")
      (libsource (lib "MP-LIBRARY") (part "Test Point"))
    )
    (comp (ref "TP418")
      (value "Test Point")
      (footprint "testpad_0.9mm")
      (description "Test pad, 0.90mm circular pad")
      (libsource (lib "MP-LIBRARY") (part "Test Point"))
    )
    (comp (ref "TP419")
      (value "Test Point")
      (footprint "testpad_0.9mm")
      (description "Test pad, 0.90mm circular pad")
      (libsource (lib "MP-LIBRARY") (part "Test Point"))
    )
    (comp (ref "TP420")
      (value "Test Point")
      (footprint "testpad_0.9mm")
      (description "Test pad, 0.90mm circular pad")
      (libsource (lib "MP-LIBRARY") (part "Test Point"))
    )
    (comp (ref "TP421")
      (value "Test Point")
      (footprint "testpad_0.9mm")
      (description "Test pad, 0.90mm circular pad")
      (libsource (lib "MP-LIBRARY") (part "Test Point"))
    )
    (comp (ref "TP422")
      (value "Test Point")
      (footprint "testpad_0.9mm")
      (description "Test pad, 0.90mm circular pad")
      (libsource (lib "MP-LIBRARY") (part "Test Point"))
    )
    (comp (ref "TP423")
      (value "Test Point")
      (footprint "testpad_0.9mm")
      (description "Test pad, 0.90mm circular pad")
      (libsource (lib "MP-LIBRARY") (part "Test Point"))
    )
    (comp (ref "TP424")
      (value "Test Point")
      (footprint "testpad_0.9mm")
      (description "Test pad, 0.90mm circular pad")
      (libsource (lib "MP-LIBRARY") (part "Test Point"))
    )
    (comp (ref "TP425")
      (value "Test Point")
      (footprint "testpad_0.9mm")
      (description "Test pad, 0.90mm circular pad")
      (libsource (lib "MP-LIBRARY") (part "Test Point"))
    )
    (comp (ref "TP426")
      (value "Test Point")
      (footprint "testpad_0.9mm")
      (description "Test pad, 0.90mm circular pad")
      (libsource (lib "MP-LIBRARY") (part "Test Point"))
    )
    (comp (ref "TP427")
      (value "Test Point")
      (footprint "testpad_0.9mm")
      (description "Test pad, 0.90mm circular pad")
      (libsource (lib "MP-LIBRARY") (part "Test Point"))
    )
    (comp (ref "TP428")
      (value "Test Point")
      (footprint "testpad_0.9mm")
      (description "Test pad, 0.90mm circular pad")
      (libsource (lib "MP-LIBRARY") (part "Test Point"))
    )
    (comp (ref "TP429")
      (value "Test Point")
      (footprint "testpad_0.9mm")
      (description "Test pad, 0.90mm circular pad")
      (libsource (lib "MP-LIBRARY") (part "Test Point"))
    )
    (comp (ref "TP430")
      (value "Test Point")
      (footprint "testpad_0.9mm")
      (description "Test pad, 0.90mm circular pad")
      (libsource (lib "MP-LIBRARY") (part "Test Point"))
    )
    (comp (ref "TP431")
      (value "Test Point")
      (footprint "testpad_0.9mm")
      (description "Test pad, 0.90mm circular pad")
      (libsource (lib "MP-LIBRARY") (part "Test Point"))
    )
    (comp (ref "TP432")
      (value "Test Point")
      (footprint "testpad_0.9mm")
      (description "Test pad, 0.90mm circular pad")
      (libsource (lib "MP-LIBRARY") (part "Test Point"))
    )
    (comp (ref "TP433")
      (value "Test Point")
      (footprint "testpad_0.9mm")
      (description "Test pad, 0.90mm circular pad")
      (libsource (lib "MP-LIBRARY") (part "Test Point"))
    )
    (comp (ref "TP434")
      (value "Test Point")
      (footprint "testpad_0.9mm")
      (description "Test pad, 0.90mm circular pad")
      (libsource (lib "MP-LIBRARY") (part "Test Point"))
    )
    (comp (ref "TP435")
      (value "Test Point")
      (footprint "testpad_0.9mm")
      (description "Test pad, 0.90mm circular pad")
      (libsource (lib "MP-LIBRARY") (part "Test Point"))
    )
    (comp (ref "U400")
      (value "LTC4065LEDC#TRMPBF")
      (footprint "LT_DC6")
      (description "Charge Controller, 4.2V, 250mA, DFN-6")
      (fields
        (field (name "MANUFACTURER") "Linear Technology")
        (field (name "MANUFACTURER PART NUMBER") "LTC4065LEDC#TRPBF")
      )
      (libsource (lib "MP-LIBRARY") (part "LTC4065LEDC#TRPBF"))
    )
    (comp (ref "U401")
      (value "TLV4021R1YKAR")
      (footprint "TI_YKA0004")
      (description "Comparator, 1.2V Reference, Open-drain, BGA-4")
      (fields (field (name "MANUFACTURER") "Texas Instruments"))
      (libsource (lib "MP-LIBRARY") (part "TLV4021R1YKAR"))
    )
    (comp (ref "U402")
      (value "LTC4065LEDC#TRMPBF")
      (footprint "LT_DC6")
      (description "Charge Controller, 4.2V, 250mA, DFN-6")
      (fields
        (field (name "MANUFACTURER") "Linear Technology")
        (field (name "MANUFACTURER PART NUMBER") "LTC4065LEDC#TRPBF")
      )
      (libsource (lib "MP-LIBRARY") (part "LTC4065LEDC#TRPBF"))
    )
    (comp (ref "U403")
      (value "TLV4021R1YKAR")
      (footprint "TI_YKA0004")
      (description "Comparator, 1.2V Reference, Open-drain, BGA-4")
      (fields (field (name "MANUFACTURER") "Texas Instruments"))
      (libsource (lib "MP-LIBRARY") (part "TLV4021R1YKAR"))
    )
    (comp (ref "U404")
      (value "AD8505ACBZ-R7")
      (footprint "AD8505ACBZ-R7")
      (description "Op Amp, Rail-to-Rail, 95kHz, WLCSP-6")
      (fields (field (name "MANUFACTURER") "Analog Devices"))
      (libsource (lib "MP-LIBRARY") (part "AD8505ACBZ-R7"))
    )
    (comp (ref "U405")
      (value "AD8505ACBZ-R7")
      (footprint "AD8505ACBZ-R7")
      (description "Op Amp, Rail-to-Rail, 95kHz, WLCSP-6")
      (fields (field (name "MANUFACTURER") "Analog Devices"))
      (libsource (lib "MP-LIBRARY") (part "AD8505ACBZ-R7"))
    )
  )
  (nets
    (net (code "3") (name "/BATT.MON1") (class "Default")
      (node (ref "TP428") (pin "1") (pinfunction "1_1") (pintype "passive"))
      (node (ref "U404") (pin "A1") (pinfunction "OUT_A1") (pintype "passive"))
      (node (ref "U404") (pin "C2") (pinfunction "IN-_C2") (pintype "passive"))
    )
    (net (code "4") (name "/BATT.MON2") (class "Default")
      (node (ref "TP429") (pin "1") (pinfunction "1_1") (pintype "passive"))
      (node (ref "U405") (pin "A1") (pinfunction "OUT_A1") (pintype "passive"))
      (node (ref "U405") (pin "C2") (pinfunction "IN-_C2") (pintype "passive"))
    )
    (net (code "5") (name "/BATT.MON_EN") (class "Default")
      (node (ref "M422") (pin "1") (pinfunction "G_1") (pintype "passive"))
      (node (ref "TP430") (pin "1") (pinfunction "1_1") (pintype "passive"))
      (node (ref "U404") (pin "A2") (pinfunction "V+_A2") (pintype "power_in"))
      (node (ref "U405") (pin "A2") (pinfunction "V+_A2") (pintype "power_in"))
    )
    (net (code "6") (name "/BATT.SW_EN") (class "Default")
      (node (ref "D422") (pin "2") (pinfunction "A_2") (pintype "passive"))
      (node (ref "TP426") (pin "1") (pinfunction "1_1") (pintype "passive"))
    )
    (net (code "7") (name "/BATT_SW") (class "Default")
      (node (ref "M419") (pin "1") (pinfunction "G_1") (pintype "passive"))
      (node (ref "R421") (pin "2") (pinfunction "2_2") (pintype "passive"))
      (node (ref "R422") (pin "2") (pinfunction "2_2") (pintype "passive"))
      (node (ref "TP427") (pin "1") (pinfunction "1_1") (pintype "passive"))
    )
    (net (code "8") (name "/CHG1.EN") (class "Default")
      (node (ref "M403") (pin "1") (pinfunction "G_1") (pintype "passive"))
      (node (ref "M404") (pin "1") (pinfunction "G_1") (pintype "passive"))
      (node (ref "R403") (pin "1") (pinfunction "1_1") (pintype "passive"))
      (node (ref "TP434") (pin "1") (pinfunction "1_1") (pintype "passive"))
    )
    (net (code "9") (name "/CHG1.OVP_ERRn") (class "Default")
      (node (ref "M406") (pin "3") (pinfunction "D_3") (pintype "passive"))
      (node (ref "R403") (pin "2") (pinfunction "2_2") (pintype "passive"))
      (node (ref "TP405") (pin "1") (pinfunction "1_1") (pintype "passive"))
    )
    (net (code "10") (name "/CHG1.STATUS") (class "Default")
      (node (ref "U400") (pin "2") (pinfunction "~{CHRG}_2") (pintype "open_collector"))
    )
    (net (code "11") (name "/CHG2.EN") (class "Default")
      (node (ref "M413") (pin "1") (pinfunction "G_1") (pintype "passive"))
      (node (ref "M414") (pin "1") (pinfunction "G_1") (pintype "passive"))
      (node (ref "R414") (pin "1") (pinfunction "1_1") (pintype "passive"))
      (node (ref "TP431") (pin "1") (pinfunction "1_1") (pintype "passive"))
    )
    (net (code "12") (name "/CHG2.OVP_ERRn") (class "Default")
      (node (ref "M415") (pin "3") (pinfunction "D_3") (pintype "passive"))
      (node (ref "R414") (pin "2") (pinfunction "2_2") (pintype "passive"))
      (node (ref "TP424") (pin "1") (pinfunction "1_1") (pintype "passive"))
    )
    (net (code "13") (name "/CHG2.STATUS") (class "Default")
      (node (ref "U402") (pin "2") (pinfunction "~{CHRG}_2") (pintype "open_collector"))
    )
    (net (code "14") (name "/CHG_RATE1") (class "Default")
      (node (ref "M407") (pin "1") (pinfunction "G_1") (pintype "passive"))
      (node (ref "M416") (pin "1") (pinfunction "G_1") (pintype "passive"))
      (node (ref "TP432") (pin "1") (pinfunction "1_1") (pintype "passive"))
    )
    (net (code "15") (name "/CHG_RATE2") (class "Default")
      (node (ref "M408") (pin "1") (pinfunction "G_1") (pintype "passive"))
      (node (ref "M417") (pin "1") (pinfunction "G_1") (pintype "passive"))
      (node (ref "TP433") (pin "1") (pinfunction "1_1") (pintype "passive"))
    )
    (net (code "16") (name "/IPG_OFF") (class "Default")
      (node (ref "M418") (pin "1") (pinfunction "G_1") (pintype "passive"))
      (node (ref "TP435") (pin "1") (pinfunction "1_1") (pintype "passive"))
    )
    (net (code "19") (name "GND") (class "Default")
      (node (ref "C400") (pin "2") (pinfunction "2_2") (pintype "passive"))
      (node (ref "C417") (pin "1") (pinfunction "1_1") (pintype "passive"))
      (node (ref "C419") (pin "1") (pinfunction "1_1") (pintype "passive"))
      (node (ref "C420") (pin "2") (pinfunction "2_2") (pintype "passive"))
      (node (ref "C422") (pin "1") (pinfunction "1_1") (pintype "passive"))
      (node (ref "C423") (pin "1") (pinfunction "1_1") (pintype "passive"))
      (node (ref "F400") (pin "2") (pinfunction "2_2") (pintype "passive"))
      (node (ref "F401") (pin "2") (pinfunction "2_2") (pintype "passive"))
      (node (ref "M403") (pin "2") (pinfunction "S_2") (pintype "passive"))
      (node (ref "M404") (pin "2") (pinfunction "S_2") (pintype "passive"))
      (node (ref "M406") (pin "2") (pinfunction "S_2") (pintype "passive"))
      (node (ref "M407") (pin "2") (pinfunction "S_2") (pintype "passive"))
      (node (ref "M408") (pin "2") (pinfunction "S_2") (pintype "passive"))
      (node (ref "M413") (pin "2") (pinfunction "S_2") (pintype "passive"))
      (node (ref "M414") (pin "2") (pinfunction "S_2") (pintype "passive"))
      (node (ref "M415") (pin "2") (pinfunction "S_2") (pintype "passive"))
      (node (ref "M416") (pin "2") (pinfunction "S_2") (pintype "passive"))
      (node (ref "M417") (pin "2") (pinfunction "S_2") (pintype "passive"))
      (node (ref "M419") (pin "2") (pinfunction "S_2") (pintype "passive"))
      (node (ref "M422") (pin "2") (pinfunction "S_2") (pintype "passive"))
      (node (ref "R404") (pin "2") (pinfunction "2_2") (pintype "passive"))
      (node (ref "R409") (pin "2") (pinfunction "2_2") (pintype "passive"))
      (node (ref "R415") (pin "2") (pinfunction "2_2") (pintype "passive"))
      (node (ref "R420") (pin "2") (pinfunction "2_2") (pintype "passive"))
      (node (ref "R422") (pin "1") (pinfunction "1_1") (pintype "passive"))
      (node (ref "R425") (pin "2") (pinfunction "2_2") (pintype "passive"))
      (node (ref "R428") (pin "2") (pinfunction "2_2") (pintype "passive"))
      (node (ref "TP408") (pin "1") (pinfunction "1_1") (pintype "passive"))
      (node (ref "TP409") (pin "1") (pinfunction "1_1") (pintype "passive"))
      (node (ref "TP410") (pin "1") (pinfunction "1_1") (pintype "passive"))
      (node (ref "TP411") (pin "1") (pinfunction "1_1") (pintype "passive"))
      (node (ref "TP412") (pin "1") (pinfunction "1_1") (pintype "passive"))
      (node (ref "TP413") (pin "1") (pinfunction "1_1") (pintype "passive"))
      (node (ref "TP414") (pin "1") (pinfunction "1_1") (pintype "passive"))
      (node (ref "TP415") (pin "1") (pinfunction "1_1") (pintype "passive"))
      (node (ref "TP416") (pin "1") (pinfunction "1_1") (pintype "passive"))
      (node (ref "TP423") (pin "1") (pinfunction "1_1") (pintype "passive"))
      (node (ref "U400") (pin "1") (pinfunction "GND_1") (pintype "power_in"))
      (node (ref "U400") (pin "5") (pinfunction "~{EN}_5") (pintype "input"))
      (node (ref "U400") (pin "7") (pinfunction "EP_7") (pintype "power_in"))
      (node (ref "U401") (pin "B2") (pinfunction "V-_B2") (pintype "power_in"))
      (node (ref "U402") (pin "1") (pinfunction "GND_1") (pintype "power_in"))
      (node (ref "U402") (pin "5") (pinfunction "~{EN}_5") (pintype "input"))
      (node (ref "U402") (pin "7") (pinfunction "EP_7") (pintype "power_in"))
      (node (ref "U403") (pin "B2") (pinfunction "V-_B2") (pintype "power_in"))
      (node (ref "U404") (pin "B1") (pinfunction "V-_B1") (pintype "power_in"))
      (node (ref "U405") (pin "B1") (pinfunction "V-_B1") (pintype "power_in"))
    )
    (net (code "20") (name "Net-(D400-A)") (class "Default")
      (node (ref "D400") (pin "2") (pinfunction "A_2") (pintype "passive"))
      (node (ref "M401") (pin "1") (pinfunction "D_1") (pintype "passive"))
      (node (ref "M402") (pin "1") (pinfunction "D_1") (pintype "passive"))
    )
    (net (code "21") (name "Net-(D419-A)") (class "Default")
      (node (ref "D419") (pin "2") (pinfunction "A_2") (pintype "passive"))
      (node (ref "M405") (pin "1") (pinfunction "G_1") (pintype "passive"))
      (node (ref "R408") (pin "2") (pinfunction "2_2") (pintype "passive"))
    )
    (net (code "22") (name "Net-(D419-K)") (class "Default")
      (node (ref "D419") (pin "1") (pinfunction "K_1") (pintype "passive"))
      (node (ref "D421") (pin "1") (pinfunction "K_1") (pintype "passive"))
      (node (ref "R418") (pin "2") (pinfunction "2_2") (pintype "passive"))
    )
    (net (code "23") (name "Net-(D420-A)") (class "Default")
      (node (ref "D420") (pin "2") (pinfunction "A_2") (pintype "passive"))
      (node (ref "M410") (pin "1") (pinfunction "D_1") (pintype "passive"))
      (node (ref "M411") (pin "1") (pinfunction "D_1") (pintype "passive"))
    )
    (net (code "24") (name "Net-(D421-A)") (class "Default")
      (node (ref "D421") (pin "2") (pinfunction "A_2") (pintype "passive"))
      (node (ref "M412") (pin "1") (pinfunction "G_1") (pintype "passive"))
      (node (ref "R413") (pin "2") (pinfunction "2_2") (pintype "passive"))
    )
    (net (code "25") (name "Net-(D422-K)") (class "Default")
      (node (ref "D422") (pin "1") (pinfunction "K_1") (pintype "passive"))
      (node (ref "R421") (pin "1") (pinfunction "1_1") (pintype "passive"))
    )
    (net (code "26") (name "Net-(D423-A)") (class "Default")
      (node (ref "D423") (pin "2") (pinfunction "A_2") (pintype "passive"))
      (node (ref "M420") (pin "1") (pinfunction "G_1") (pintype "passive"))
      (node (ref "R423") (pin "2") (pinfunction "2_2") (pintype "passive"))
    )
    (net (code "27") (name "Net-(D423-K)") (class "Default")
      (node (ref "D423") (pin "1") (pinfunction "K_1") (pintype "passive"))
      (node (ref "D424") (pin "1") (pinfunction "K_1") (pintype "passive"))
      (node (ref "M422") (pin "3") (pinfunction "D_3") (pintype "passive"))
    )
    (net (code "28") (name "Net-(D424-A)") (class "Default")
      (node (ref "D424") (pin "2") (pinfunction "A_2") (pintype "passive"))
      (node (ref "M421") (pin "1") (pinfunction "G_1") (pintype "passive"))
      (node (ref "R426") (pin "2") (pinfunction "2_2") (pintype "passive"))
    )
    (net (code "29") (name "Net-(M400-D)") (class "Default")
      (node (ref "C400") (pin "1") (pinfunction "1_1") (pintype "passive"))
      (node (ref "M400") (pin "3") (pinfunction "D_3") (pintype "passive"))
      (node (ref "TP400") (pin "1") (pinfunction "1_1") (pintype "passive"))
      (node (ref "U400") (pin "4") (pinfunction "VCC_4") (pintype "power_in"))
    )
    (net (code "30") (name "Net-(M400-G)") (class "Default")
      (node (ref "M400") (pin "1") (pinfunction "G_1") (pintype "passive"))
      (node (ref "M404") (pin "3") (pinfunction "D_3") (pintype "passive"))
      (node (ref "R400") (pin "2") (pinfunction "2_2") (pintype "passive"))
    )
    (net (code "31") (name "Net-(M401-G)") (class "Default")
      (node (ref "M401") (pin "2") (pinfunction "G_2") (pintype "passive"))
      (node (ref "M406") (pin "1") (pinfunction "G_1") (pintype "passive"))
      (node (ref "R402") (pin "2") (pinfunction "2_2") (pintype "passive"))
      (node (ref "TP406") (pin "1") (pinfunction "1_1") (pintype "passive"))
      (node (ref "U401") (pin "A1") (pinfunction "OUT_A1") (pintype "power_in"))
    )
    (net (code "32") (name "Net-(M402-G)") (class "Default")
      (node (ref "M402") (pin "2") (pinfunction "G_2") (pintype "passive"))
      (node (ref "M403") (pin "3") (pinfunction "D_3") (pintype "passive"))
      (node (ref "R401") (pin "2") (pinfunction "2_2") (pintype "passive"))
    )
    (net (code "33") (name "Net-(M407-D)") (class "Default")
      (node (ref "M407") (pin "3") (pinfunction "D_3") (pintype "passive"))
      (node (ref "R405") (pin "2") (pinfunction "2_2") (pintype "passive"))
    )
    (net (code "34") (name "Net-(M408-D)") (class "Default")
      (node (ref "M408") (pin "3") (pinfunction "D_3") (pintype "passive"))
      (node (ref "R406") (pin "2") (pinfunction "2_2") (pintype "passive"))
    )
    (net (code "35") (name "Net-(M409-D)") (class "Default")
      (node (ref "C420") (pin "1") (pinfunction "1_1") (pintype "passive"))
      (node (ref "M409") (pin "3") (pinfunction "D_3") (pintype "passive"))
      (node (ref "TP417") (pin "1") (pinfunction "1_1") (pintype "passive"))
      (node (ref "U402") (pin "4") (pinfunction "VCC_4") (pintype "power_in"))
    )
    (net (code "36") (name "Net-(M409-G)") (class "Default")
      (node (ref "M409") (pin "1") (pinfunction "G_1") (pintype "passive"))
      (node (ref "M414") (pin "3") (pinfunction "D_3") (pintype "passive"))
      (node (ref "R410") (pin "2") (pinfunction "2_2") (pintype "passive"))
    )
    (net (code "37") (name "Net-(M410-G)") (class "Default")
      (node (ref "M410") (pin "2") (pinfunction "G_2") (pintype "passive"))
      (node (ref "M415") (pin "1") (pinfunction "G_1") (pintype "passive"))
      (node (ref "R412") (pin "2") (pinfunction "2_2") (pintype "passive"))
      (node (ref "TP425") (pin "1") (pinfunction "1_1") (pintype "passive"))
      (node (ref "U403") (pin "A1") (pinfunction "OUT_A1") (pintype "power_in"))
    )
    (net (code "38") (name "Net-(M411-G)") (class "Default")
      (node (ref "M411") (pin "2") (pinfunction "G_2") (pintype "passive"))
      (node (ref "M413") (pin "3") (pinfunction "D_3") (pintype "passive"))
      (node (ref "R411") (pin "2") (pinfunction "2_2") (pintype "passive"))
    )
    (net (code "39") (name "Net-(M416-D)") (class "Default")
      (node (ref "M416") (pin "3") (pinfunction "D_3") (pintype "passive"))
      (node (ref "R416") (pin "2") (pinfunction "2_2") (pintype "passive"))
    )
    (net (code "40") (name "Net-(M417-D)") (class "Default")
      (node (ref "M417") (pin "3") (pinfunction "D_3") (pintype "passive"))
      (node (ref "R417") (pin "2") (pinfunction "2_2") (pintype "passive"))
    )
    (net (code "41") (name "Net-(M418-D)") (class "Default")
      (node (ref "M418") (pin "3") (pinfunction "D_3") (pintype "passive"))
      (node (ref "R418") (pin "1") (pinfunction "1_1") (pintype "passive"))
    )
    (net (code "42") (name "Net-(M418-S)") (class "Default")
      (node (ref "M418") (pin "2") (pinfunction "S_2") (pintype "passive"))
      (node (ref "M419") (pin "3") (pinfunction "D_3") (pintype "passive"))
    )
    (net (code "43") (name "Net-(M420-D)") (class "Default")
      (node (ref "M420") (pin "3") (pinfunction "D_3") (pintype "passive"))
      (node (ref "R424") (pin "1") (pinfunction "1_1") (pintype "passive"))
    )
    (net (code "44") (name "Net-(M421-D)") (class "Default")
      (node (ref "M421") (pin "3") (pinfunction "D_3") (pintype "passive"))
      (node (ref "R427") (pin "1") (pinfunction "1_1") (pintype "passive"))
    )
    (net (code "45") (name "Net-(U400-PROG)") (class "Default")
      (node (ref "R404") (pin "1") (pinfunction "1_1") (pintype "passive"))
      (node (ref "R405") (pin "1") (pinfunction "1_1") (pintype "passive"))
      (node (ref "R406") (pin "1") (pinfunction "1_1") (pintype "passive"))
      (node (ref "U400") (pin "6") (pinfunction "PROG_6") (pintype "passive"))
    )
    (net (code "46") (name "Net-(U401-IN)") (class "Default")
      (node (ref "C419") (pin "2") (pinfunction "2_2") (pintype "passive"))
      (node (ref "R407") (pin "2") (pinfunction "2_2") (pintype "passive"))
      (node (ref "R409") (pin "1") (pinfunction "1_1") (pintype "passive"))
      (node (ref "U401") (pin "A2") (pinfunction "IN_A2") (pintype "passive"))
    )
    (net (code "47") (name "Net-(U402-PROG)") (class "Default")
      (node (ref "R415") (pin "1") (pinfunction "1_1") (pintype "passive"))
      (node (ref "R416") (pin "1") (pinfunction "1_1") (pintype "passive"))
      (node (ref "R417") (pin "1") (pinfunction "1_1") (pintype "passive"))
      (node (ref "U402") (pin "6") (pinfunction "PROG_6") (pintype "passive"))
    )
    (net (code "48") (name "Net-(U403-IN)") (class "Default")
      (node (ref "C423") (pin "2") (pinfunction "2_2") (pintype "passive"))
      (node (ref "R419") (pin "2") (pinfunction "2_2") (pintype "passive"))
      (node (ref "R420") (pin "1") (pinfunction "1_1") (pintype "passive"))
      (node (ref "U403") (pin "A2") (pinfunction "IN_A2") (pintype "passive"))
    )
    (net (code "49") (name "Net-(U404-IN+)") (class "Default")
      (node (ref "R424") (pin "2") (pinfunction "2_2") (pintype "passive"))
      (node (ref "R425") (pin "1") (pinfunction "1_1") (pintype "passive"))
      (node (ref "U404") (pin "C1") (pinfunction "IN+_C1") (pintype "passive"))
    )
    (net (code "50") (name "Net-(U405-IN+)") (class "Default")
      (node (ref "R427") (pin "2") (pinfunction "2_2") (pintype "passive"))
      (node (ref "R428") (pin "1") (pinfunction "1_1") (pintype "passive"))
      (node (ref "U405") (pin "C1") (pinfunction "IN+_C1") (pintype "passive"))
    )
    (net (code "51") (name "VBAT1CHG") (class "Default")
      (node (ref "M401") (pin "3") (pinfunction "S_3") (pintype "passive"))
      (node (ref "R402") (pin "1") (pinfunction "1_1") (pintype "passive"))
      (node (ref "R407") (pin "1") (pinfunction "1_1") (pintype "passive"))
      (node (ref "TP401") (pin "1") (pinfunction "1_1") (pintype "passive"))
      (node (ref "U400") (pin "3") (pinfunction "BAT_3") (pintype "power_in"))
    )
    (net (code "52") (name "VBAT1F") (class "Default")
      (node (ref "D400") (pin "1") (pinfunction "K_1") (pintype "passive"))
      (node (ref "L400") (pin "2") (pinfunction "2_2") (pintype "passive"))
      (node (ref "M402") (pin "3") (pinfunction "S_3") (pintype "passive"))
      (node (ref "M405") (pin "2") (pinfunction "S_2") (pintype "passive"))
      (node (ref "R401") (pin "1") (pinfunction "1_1") (pintype "passive"))
      (node (ref "R408") (pin "1") (pinfunction "1_1") (pintype "passive"))
      (node (ref "R429") (pin "2") (pinfunction "2_2") (pintype "passive"))
      (node (ref "TP403") (pin "1") (pinfunction "1_1") (pintype "passive"))
    )
    (net (code "53") (name "VBAT1R") (class "Default")
      (node (ref "J400") (pin "1") (pinfunction "1_1") (pintype "passive"))
      (node (ref "J400") (pin "2") (pinfunction "2_2") (pintype "passive"))
      (node (ref "J400") (pin "3") (pinfunction "3_3") (pintype "passive"))
      (node (ref "J400") (pin "4") (pinfunction "4_4") (pintype "passive"))
      (node (ref "J421") (pin "2") (pinfunction "2_2") (pintype "passive"))
      (node (ref "L400") (pin "1") (pinfunction "1_1") (pintype "passive"))
      (node (ref "R429") (pin "1") (pinfunction "1_1") (pintype "passive"))
      (node (ref "TP402") (pin "1") (pinfunction "1_1") (pintype "passive"))
    )
    (net (code "54") (name "VBAT1SW") (class "Default")
      (node (ref "M405") (pin "3") (pinfunction "D_3") (pintype "passive"))
      (node (ref "M420") (pin "2") (pinfunction "S_2") (pintype "passive"))
      (node (ref "R423") (pin "1") (pinfunction "1_1") (pintype "passive"))
      (node (ref "TP404") (pin "1") (pinfunction "1_1") (pintype "passive"))
    )
    (net (code "55") (name "VBAT2CHG") (class "Default")
      (node (ref "M410") (pin "3") (pinfunction "S_3") (pintype "passive"))
      (node (ref "R412") (pin "1") (pinfunction "1_1") (pintype "passive"))
      (node (ref "R419") (pin "1") (pinfunction "1_1") (pintype "passive"))
      (node (ref "TP418") (pin "1") (pinfunction "1_1") (pintype "passive"))
      (node (ref "U402") (pin "3") (pinfunction "BAT_3") (pintype "power_in"))
    )
    (net (code "56") (name "VBAT2F") (class "Default")
      (node (ref "D420") (pin "1") (pinfunction "K_1") (pintype "passive"))
      (node (ref "L401") (pin "2") (pinfunction "2_2") (pintype "passive"))
      (node (ref "M411") (pin "3") (pinfunction "S_3") (pintype "passive"))
      (node (ref "M412") (pin "2") (pinfunction "S_2") (pintype "passive"))
      (node (ref "R411") (pin "1") (pinfunction "1_1") (pintype "passive"))
      (node (ref "R413") (pin "1") (pinfunction "1_1") (pintype "passive"))
      (node (ref "R430") (pin "2") (pinfunction "2_2") (pintype "passive"))
      (node (ref "TP420") (pin "1") (pinfunction "1_1") (pintype "passive"))
    )
    (net (code "57") (name "VBAT2R") (class "Default")
      (node (ref "J422") (pin "1") (pinfunction "1_1") (pintype "passive"))
      (node (ref "J422") (pin "2") (pinfunction "2_2") (pintype "passive"))
      (node (ref "J422") (pin "3") (pinfunction "3_3") (pintype "passive"))
      (node (ref "J422") (pin "4") (pinfunction "4_4") (pintype "passive"))
      (node (ref "J424") (pin "2") (pinfunction "2_2") (pintype "passive"))
      (node (ref "L401") (pin "1") (pinfunction "1_1") (pintype "passive"))
      (node (ref "R430") (pin "1") (pinfunction "1_1") (pintype "passive"))
      (node (ref "TP419") (pin "1") (pinfunction "1_1") (pintype "passive"))
    )
    (net (code "58") (name "VBAT2SW") (class "Default")
      (node (ref "M412") (pin "3") (pinfunction "D_3") (pintype "passive"))
      (node (ref "M421") (pin "2") (pinfunction "S_2") (pintype "passive"))
      (node (ref "R426") (pin "1") (pinfunction "1_1") (pintype "passive"))
      (node (ref "TP421") (pin "1") (pinfunction "1_1") (pintype "passive"))
    )
    (net (code "59") (name "VCHG_RAIL") (class "Default")
      (node (ref "C417") (pin "2") (pinfunction "2_2") (pintype "passive"))
      (node (ref "C422") (pin "2") (pinfunction "2_2") (pintype "passive"))
      (node (ref "M400") (pin "2") (pinfunction "S_2") (pintype "passive"))
      (node (ref "M409") (pin "2") (pinfunction "S_2") (pintype "passive"))
      (node (ref "R400") (pin "1") (pinfunction "1_1") (pintype "passive"))
      (node (ref "R410") (pin "1") (pinfunction "1_1") (pintype "passive"))
      (node (ref "U401") (pin "B1") (pinfunction "V+_B1") (pintype "power_in"))
      (node (ref "U403") (pin "B1") (pinfunction "V+_B1") (pintype "power_in"))
    )
    (net (code "60") (name "VGND1R") (class "Default")
      (node (ref "F400") (pin "1") (pinfunction "1_1") (pintype "passive"))
      (node (ref "J420") (pin "1") (pinfunction "1_1") (pintype "passive"))
      (node (ref "J420") (pin "2") (pinfunction "2_2") (pintype "passive"))
      (node (ref "J420") (pin "3") (pinfunction "3_3") (pintype "passive"))
      (node (ref "J420") (pin "4") (pinfunction "4_4") (pintype "passive"))
      (node (ref "J421") (pin "4") (pinfunction "4_4") (pintype "passive"))
      (node (ref "TP407") (pin "1") (pinfunction "1_1") (pintype "passive"))
    )
    (net (code "61") (name "VGND2R") (class "Default")
      (node (ref "F401") (pin "1") (pinfunction "1_1") (pintype "passive"))
      (node (ref "J423") (pin "1") (pinfunction "1_1") (pintype "passive"))
      (node (ref "J423") (pin "2") (pinfunction "2_2") (pintype "passive"))
      (node (ref "J423") (pin "3") (pinfunction "3_3") (pintype "passive"))
      (node (ref "J423") (pin "4") (pinfunction "4_4") (pintype "passive"))
      (node (ref "J424") (pin "4") (pinfunction "4_4") (pintype "passive"))
      (node (ref "TP422") (pin "1") (pinfunction "1_1") (pintype "passive"))
    )
    (net (code "62") (name "unconnected-(J421-Pad1)") (class "Default")
      (node (ref "J421") (pin "1") (pinfunction "1_1") (pintype "passive+no_connect"))
    )
    (net (code "63") (name "unconnected-(J421-Pad3)") (class "Default")
      (node (ref "J421") (pin "3") (pinfunction "3_3") (pintype "passive+no_connect"))
    )
    (net (code "64") (name "unconnected-(J424-Pad1)") (class "Default")
      (node (ref "J424") (pin "1") (pinfunction "1_1") (pintype "passive+no_connect"))
    )
    (net (code "65") (name "unconnected-(J424-Pad3)") (class "Default")
      (node (ref "J424") (pin "3") (pinfunction "3_3") (pintype "passive+no_connect"))
    )
    (net (code "66") (name "unconnected-(U404-NC-PadB2)") (class "Default")
      (node (ref "U404") (pin "B2") (pinfunction "NC_B2") (pintype "power_in+no_connect"))
    )
    (net (code "67") (name "unconnected-(U405-NC-PadB2)") (class "Default")
      (node (ref "U405") (pin "B2") (pinfunction "NC_B2") (pintype "power_in+no_connect"))
    )
  )
)
